# MCU.net
KiCad netlist of a schematic drawn in Altium Designer
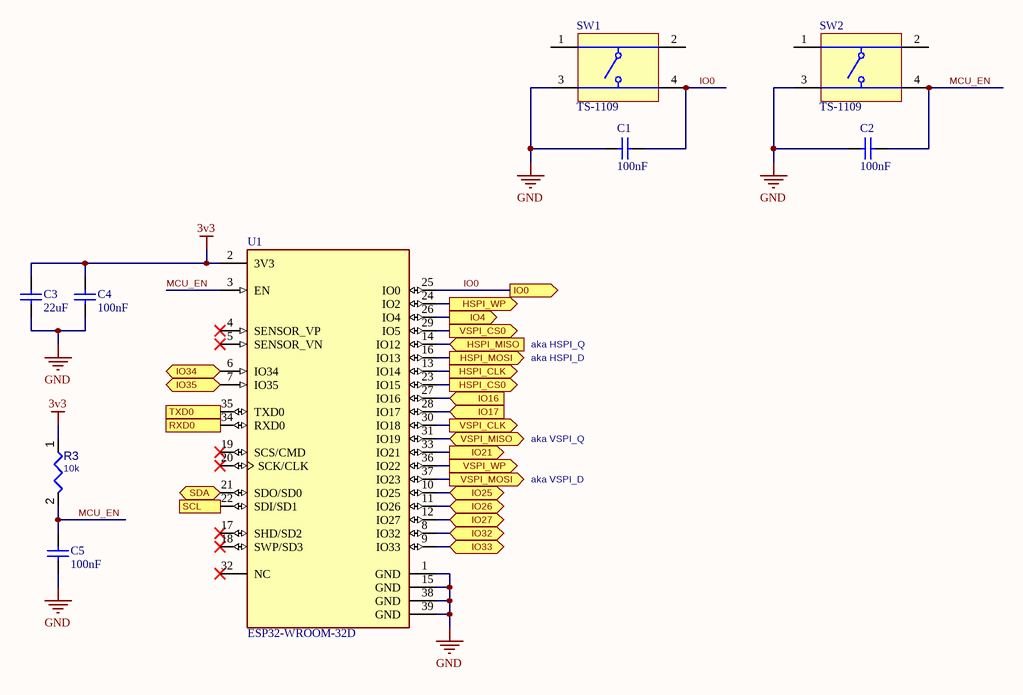
[diagram p0: MCU.SchDoc]

(export (version "E")
  (design (tool "Eeschema 10.0.6"))
  (components
    (comp (ref "C1")
      (value "GRM155R71E104KE14D")
      (footprint "Capacitor_0402")
      (description "Chip Capacitor 100nF 0402 25V X7R")
      (fields (field (name "CAPACITANCE") "100nF"))
      (libsource (lib "RIT Launch Initiative") (part "CAPACITOR"))
    )
    (comp (ref "C2")
      (value "GRM155R71E104KE14D")
      (footprint "Capacitor_0402")
      (description "Chip Capacitor 100nF 0402 25V X7R")
      (fields (field (name "CAPACITANCE") "100nF"))
      (libsource (lib "RIT Launch Initiative") (part "CAPACITOR"))
    )
    (comp (ref "C3")
      (value "GRM188R61A226ME15D")
      (footprint "Capacitor_0603")
      (description "0603 22 uF 10 V ±20% Tolerance X5R Multilayer Ceramic Chip Capacitor")
      (fields (field (name "CAPACITANCE") "22uF") (field (name "TOLERANCE") "20%"))
      (libsource (lib "RIT Launch Initiative") (part "CAPACITOR"))
    )
    (comp (ref "C4")
      (value "GRM155R71E104KE14D")
      (footprint "Capacitor_0402")
      (description "Chip Capacitor 100nF 0402 25V X7R")
      (fields (field (name "CAPACITANCE") "100nF"))
      (libsource (lib "RIT Launch Initiative") (part "CAPACITOR"))
    )
    (comp (ref "C5")
      (value "GRM155R71E104KE14D")
      (footprint "Capacitor_0402")
      (description "Chip Capacitor 100nF 0402 25V X7R")
      (fields (field (name "CAPACITANCE") "100nF"))
      (libsource (lib "RIT Launch Initiative") (part "CAPACITOR"))
    )
    (comp (ref "R3")
      (value "10k")
      (footprint "RESC0402(1005)_L")
      (description "Chip Resistor, 10 kOhms, +/-1 %, 63 mW, -55 to 125 degC, 0402")
      (fields (field (name "POWER") "63mW") (field (name "TOLERANCE") "1%"))
      (libsource (lib "RIT Launch Initiative") (part "RES-2"))
    )
    (comp (ref "SW1")
      (value "TS-1109")
      (footprint "BEST-TS-1109_V")
      (description "Tactile Switch, SPST, 12 V, 50 mA, -20 to 80 degC, 4-Pin THD")
      (fields (field (name "MANUFACTURER") "Shenzhen Best"))
      (libsource (lib "RIT Launch Initiative") (part "SW-SPST-4_A"))
    )
    (comp (ref "SW2")
      (value "TS-1109")
      (footprint "BEST-TS-1109_V")
      (description "Tactile Switch, SPST, 12 V, 50 mA, -20 to 80 degC, 4-Pin THD")
      (fields (field (name "MANUFACTURER") "Shenzhen Best"))
      (libsource (lib "RIT Launch Initiative") (part "SW-SPST-4_A"))
    )
    (comp (ref "U1")
      (value "ESP32-WROOM-32D")
      (footprint "ESP32-WROOM-32D-Footprint-1")
      (libsource (lib "RIT Launch Initiative") (part "ESP32-WROOM-32D"))
    )
  )
  (nets
    (net (code "1") (name "/HSPI_CLK") (class "Default")
      (node (ref "U1") (pin "13") (pinfunction "IO14_13") (pintype "bidirectional"))
    )
    (net (code "2") (name "/HSPI_CS0") (class "Default")
      (node (ref "U1") (pin "23") (pinfunction "IO15_23") (pintype "bidirectional"))
    )
    (net (code "3") (name "/HSPI_MISO") (class "Default")
      (node (ref "U1") (pin "14") (pinfunction "IO12_14") (pintype "bidirectional"))
    )
    (net (code "4") (name "/HSPI_MOSI") (class "Default")
      (node (ref "U1") (pin "16") (pinfunction "IO13_16") (pintype "bidirectional"))
    )
    (net (code "5") (name "/HSPI_WP") (class "Default")
      (node (ref "U1") (pin "24") (pinfunction "IO2_24") (pintype "bidirectional"))
    )
    (net (code "6") (name "/IO0") (class "Default")
      (node (ref "C1") (pin "1") (pinfunction "1_1") (pintype "passive"))
      (node (ref "SW1") (pin "4") (pinfunction "4_4") (pintype "passive"))
      (node (ref "U1") (pin "25") (pinfunction "IO0_25") (pintype "bidirectional"))
    )
    (net (code "7") (name "/IO4") (class "Default")
      (node (ref "U1") (pin "26") (pinfunction "IO4_26") (pintype "bidirectional"))
    )
    (net (code "8") (name "/IO16") (class "Default")
      (node (ref "U1") (pin "27") (pinfunction "IO16_27") (pintype "bidirectional"))
    )
    (net (code "9") (name "/IO17") (class "Default")
      (node (ref "U1") (pin "28") (pinfunction "IO17_28") (pintype "bidirectional"))
    )
    (net (code "10") (name "/IO21") (class "Default")
      (node (ref "U1") (pin "33") (pinfunction "IO21_33") (pintype "bidirectional"))
    )
    (net (code "11") (name "/IO25") (class "Default")
      (node (ref "U1") (pin "10") (pinfunction "IO25_10") (pintype "bidirectional"))
    )
    (net (code "12") (name "/IO26") (class "Default")
      (node (ref "U1") (pin "11") (pinfunction "IO26_11") (pintype "bidirectional"))
    )
    (net (code "13") (name "/IO27") (class "Default")
      (node (ref "U1") (pin "12") (pinfunction "IO27_12") (pintype "bidirectional"))
    )
    (net (code "14") (name "/IO32") (class "Default")
      (node (ref "U1") (pin "8") (pinfunction "IO32_8") (pintype "bidirectional"))
    )
    (net (code "15") (name "/IO33") (class "Default")
      (node (ref "U1") (pin "9") (pinfunction "IO33_9") (pintype "bidirectional"))
    )
    (net (code "16") (name "/IO34") (class "Default")
      (node (ref "U1") (pin "6") (pinfunction "IO34_6") (pintype "input"))
    )
    (net (code "17") (name "/IO35") (class "Default")
      (node (ref "U1") (pin "7") (pinfunction "IO35_7") (pintype "input"))
    )
    (net (code "18") (name "/MCU_EN") (class "Default")
      (node (ref "C2") (pin "1") (pinfunction "1_1") (pintype "passive"))
      (node (ref "C5") (pin "2") (pinfunction "2_2") (pintype "passive"))
      (node (ref "R3") (pin "2") (pinfunction "2_2") (pintype "passive"))
      (node (ref "SW2") (pin "4") (pinfunction "4_4") (pintype "passive"))
      (node (ref "U1") (pin "3") (pinfunction "EN_3") (pintype "input"))
    )
    (net (code "19") (name "/RXD0") (class "Default")
      (node (ref "U1") (pin "34") (pinfunction "RXD0_34") (pintype "bidirectional"))
    )
    (net (code "20") (name "/SCL") (class "Default")
      (node (ref "U1") (pin "22") (pinfunction "SDI/SD1_22") (pintype "bidirectional"))
    )
    (net (code "21") (name "/SDA") (class "Default")
      (node (ref "U1") (pin "21") (pinfunction "SDO/SD0_21") (pintype "bidirectional"))
    )
    (net (code "22") (name "/TXD0") (class "Default")
      (node (ref "U1") (pin "35") (pinfunction "TXD0_35") (pintype "bidirectional"))
    )
    (net (code "23") (name "/VSPI_CLK") (class "Default")
      (node (ref "U1") (pin "30") (pinfunction "IO18_30") (pintype "bidirectional"))
    )
    (net (code "24") (name "/VSPI_CS0") (class "Default")
      (node (ref "U1") (pin "29") (pinfunction "IO5_29") (pintype "bidirectional"))
    )
    (net (code "25") (name "/VSPI_MISO") (class "Default")
      (node (ref "U1") (pin "31") (pinfunction "IO19_31") (pintype "bidirectional"))
    )
    (net (code "26") (name "/VSPI_MOSI") (class "Default")
      (node (ref "U1") (pin "37") (pinfunction "IO23_37") (pintype "bidirectional"))
    )
    (net (code "27") (name "/VSPI_WP") (class "Default")
      (node (ref "U1") (pin "36") (pinfunction "IO22_36") (pintype "bidirectional"))
    )
    (net (code "28") (name "3v3") (class "Default")
      (node (ref "C3") (pin "2") (pinfunction "2_2") (pintype "passive"))
      (node (ref "C4") (pin "2") (pinfunction "2_2") (pintype "passive"))
      (node (ref "R3") (pin "1") (pinfunction "1_1") (pintype "passive"))
      (node (ref "U1") (pin "2") (pinfunction "3V3_2") (pintype "power_in"))
    )
    (net (code "29") (name "GND") (class "Default")
      (node (ref "C1") (pin "2") (pinfunction "2_2") (pintype "passive"))
      (node (ref "C2") (pin "2") (pinfunction "2_2") (pintype "passive"))
      (node (ref "C3") (pin "1") (pinfunction "1_1") (pintype "passive"))
      (node (ref "C4") (pin "1") (pinfunction "1_1") (pintype "passive"))
      (node (ref "C5") (pin "1") (pinfunction "1_1") (pintype "passive"))
      (node (ref "SW1") (pin "3") (pinfunction "3_3") (pintype "passive"))
      (node (ref "SW2") (pin "3") (pinfunction "3_3") (pintype "passive"))
      (node (ref "U1") (pin "1") (pinfunction "GND_1") (pintype "power_in"))
      (node (ref "U1") (pin "15") (pinfunction "GND_15") (pintype "power_in"))
      (node (ref "U1") (pin "38") (pinfunction "GND_38") (pintype "power_in"))
      (node (ref "U1") (pin "39") (pinfunction "GND_39") (pintype "power_in"))
    )
    (net (code "30") (name "unconnected-(SW1-Pad1)") (class "Default")
      (node (ref "SW1") (pin "1") (pinfunction "1_1") (pintype "passive"))
    )
    (net (code "31") (name "unconnected-(SW1-Pad2)") (class "Default")
      (node (ref "SW1") (pin "2") (pinfunction "2_2") (pintype "passive"))
    )
    (net (code "32") (name "unconnected-(SW2-Pad1)") (class "Default")
      (node (ref "SW2") (pin "1") (pinfunction "1_1") (pintype "passive"))
    )
    (net (code "33") (name "unconnected-(SW2-Pad2)") (class "Default")
      (node (ref "SW2") (pin "2") (pinfunction "2_2") (pintype "passive"))
    )
    (net (code "34") (name "unconnected-(U1-NC-Pad32)") (class "Default")
      (node (ref "U1") (pin "32") (pinfunction "NC_32") (pintype "open_emitter+no_connect"))
    )
    (net (code "35") (name "unconnected-(U1-SCK{slash}CLK-Pad20)") (class "Default")
      (node (ref "U1") (pin "20") (pinfunction "SCK/CLK_20") (pintype "bidirectional+no_connect"))
    )
    (net (code "36") (name "unconnected-(U1-SCS{slash}CMD-Pad19)") (class "Default")
      (node (ref "U1") (pin "19") (pinfunction "SCS/CMD_19") (pintype "bidirectional+no_connect"))
    )
    (net (code "37") (name "unconnected-(U1-SENSOR_VN-Pad5)") (class "Default")
      (node (ref "U1") (pin "5") (pinfunction "SENSOR_VN_5") (pintype "input+no_connect"))
    )
    (net (code "38") (name "unconnected-(U1-SENSOR_VP-Pad4)") (class "Default")
      (node (ref "U1") (pin "4") (pinfunction "SENSOR_VP_4") (pintype "input+no_connect"))
    )
    (net (code "39") (name "unconnected-(U1-SHD{slash}SD2-Pad17)") (class "Default")
      (node (ref "U1") (pin "17") (pinfunction "SHD/SD2_17") (pintype "bidirectional+no_connect"))
    )
    (net (code "40") (name "unconnected-(U1-SWP{slash}SD3-Pad18)") (class "Default")
      (node (ref "U1") (pin "18") (pinfunction "SWP/SD3_18") (pintype "bidirectional+no_connect"))
    )
  )
)
